# KIS_3R33S_vreg.net
KiCad netlist of a schematic drawn in EAGLE
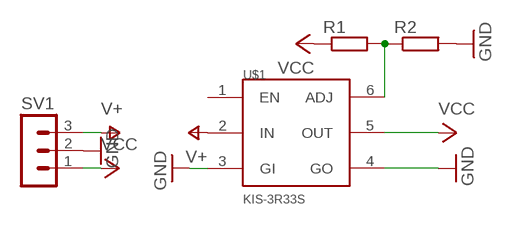
[diagram p0: schematic, sheet 1]

(export (version "E")
  (design (tool "Eeschema 10.0.6"))
  (components
    (comp (ref "R1")
      (value "R-EU_R1206W")
      (footprint "eagle-import:R1206W")
      (libsource (lib "eagle-import") (part "R-EU_R1206W"))
    )
    (comp (ref "R2")
      (value "R-EU_R1206W")
      (footprint "eagle-import:R1206W")
      (libsource (lib "eagle-import") (part "R-EU_R1206W"))
    )
    (comp (ref "SV1")
      (value "MA03-1")
      (footprint "eagle-import:MA03-1")
      (libsource (lib "eagle-import") (part "MA03-1"))
    )
    (comp (ref "U$1")
      (value "KIS-3R33S")
      (footprint "eagle-import:KIS-3R33S")
      (libsource (lib "eagle-import") (part "KIS-3R33S"))
    )
  )
  (nets
    (net (code "1") (name "GND") (class "Default")
      (node (ref "R2") (pin "2") (pinfunction "2_2") (pintype "passive"))
      (node (ref "SV1") (pin "2") (pinfunction "2_2") (pintype "passive"))
      (node (ref "U$1") (pin "3") (pinfunction "GI_3") (pintype "power_in"))
      (node (ref "U$1") (pin "4") (pinfunction "GO_4") (pintype "power_in"))
    )
    (net (code "2") (name "Net-(U$1-ADJ)") (class "Default")
      (node (ref "R1") (pin "2") (pinfunction "2_2") (pintype "passive"))
      (node (ref "R2") (pin "1") (pinfunction "1_1") (pintype "passive"))
      (node (ref "U$1") (pin "6") (pinfunction "ADJ_6") (pintype "bidirectional"))
    )
    (net (code "3") (name "V+") (class "Default")
      (node (ref "SV1") (pin "3") (pinfunction "3_3") (pintype "passive"))
      (node (ref "U$1") (pin "2") (pinfunction "IN_2") (pintype "bidirectional"))
    )
    (net (code "4") (name "VCC") (class "Default")
      (node (ref "R1") (pin "1") (pinfunction "1_1") (pintype "passive"))
      (node (ref "SV1") (pin "1") (pinfunction "1_1") (pintype "passive"))
      (node (ref "U$1") (pin "5") (pinfunction "OUT_5") (pintype "bidirectional"))
    )
    (net (code "5") (name "unconnected-(U$1-EN-Pad1)") (class "Default")
      (node (ref "U$1") (pin "1") (pinfunction "EN_1") (pintype "bidirectional"))
    )
  )
)
